# Motor_Shield.net
KiCad netlist of a schematic drawn in EAGLE
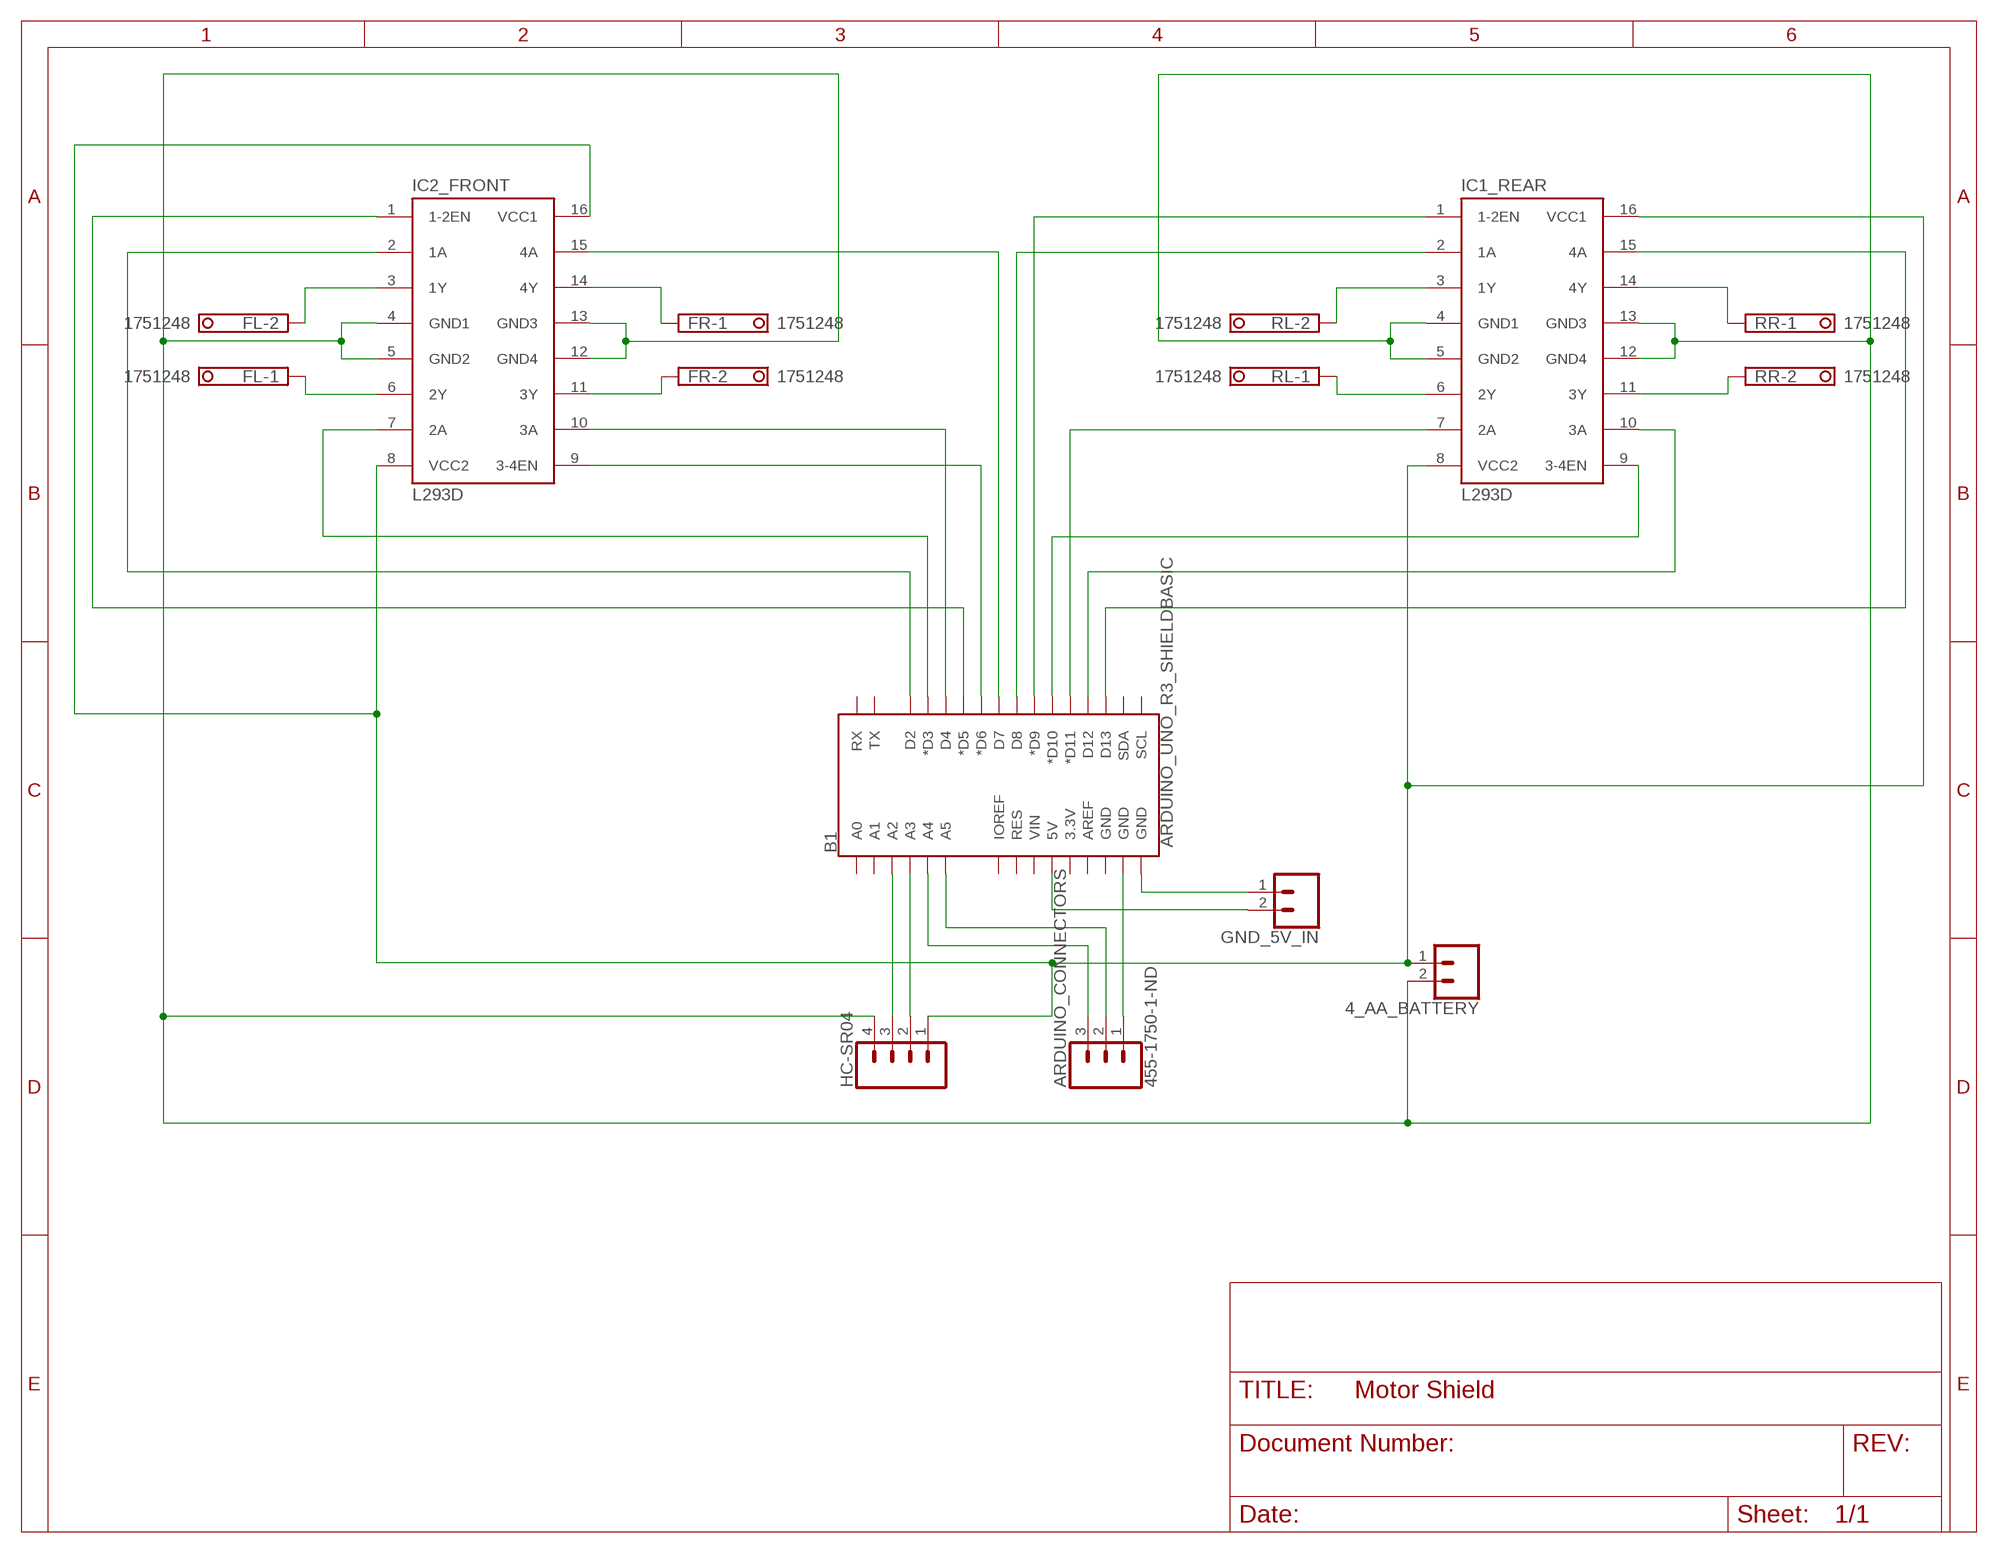
[diagram p0: schematic, sheet 1]

(export (version "E")
  (design (tool "Eeschema 10.0.6"))
  (components
    (comp (ref "4_AA_BATTERY")
      (value "CONN_02")
      (footprint "eagle-import:1X02")
      (libsource (lib "eagle-import") (part "CONN_02"))
    )
    (comp (ref "ARDUINO_CONNECTORS")
      (value "455-1750-1-ND")
      (footprint "eagle-import:1X03")
      (libsource (lib "eagle-import") (part "CONN_03"))
    )
    (comp (ref "B1")
      (value "ARDUINO_UNO_R3_SHIELDBASIC")
      (footprint "eagle-import:UNO_R3_SHIELD")
      (libsource (lib "eagle-import") (part "ARDUINO_UNO_R3_SHIELDBASIC"))
    )
    (comp (ref "FL")
      (value "1751248")
      (footprint "eagle-import:1751248")
      (libsource (lib "eagle-import") (part "1751248"))
    )
    (comp (ref "FR")
      (value "1751248")
      (footprint "eagle-import:1751248")
      (libsource (lib "eagle-import") (part "1751248"))
    )
    (comp (ref "GND_5V_IN")
      (value "CONN_02")
      (footprint "eagle-import:1X02")
      (libsource (lib "eagle-import") (part "CONN_02"))
    )
    (comp (ref "HC-SR04")
      (value "CONN_04PTH")
      (footprint "eagle-import:1X04")
      (libsource (lib "eagle-import") (part "CONN_04PTH"))
    )
    (comp (ref "IC1_REAR")
      (value "L293D")
      (footprint "eagle-import:DIL16")
      (libsource (lib "eagle-import") (part "L293D"))
    )
    (comp (ref "IC2_FRONT")
      (value "L293D")
      (footprint "eagle-import:DIL16")
      (libsource (lib "eagle-import") (part "L293D"))
    )
    (comp (ref "RL")
      (value "1751248")
      (footprint "eagle-import:1751248")
      (libsource (lib "eagle-import") (part "1751248"))
    )
    (comp (ref "RR")
      (value "1751248")
      (footprint "eagle-import:1751248")
      (libsource (lib "eagle-import") (part "1751248"))
    )
  )
  (nets
    (net (code "1") (name "Net-(ARDUINO_CONNECTORS-Pad1)") (class "Default")
      (node (ref "ARDUINO_CONNECTORS") (pin "1") (pinfunction "1_1") (pintype "passive"))
      (node (ref "B1") (pin "GND@1") (pinfunction "GND_GND@1") (pintype "bidirectional"))
    )
    (net (code "2") (name "Net-(ARDUINO_CONNECTORS-Pad2)") (class "Default")
      (node (ref "ARDUINO_CONNECTORS") (pin "2") (pinfunction "2_2") (pintype "passive"))
      (node (ref "B1") (pin "A5") (pinfunction "A5_A5") (pintype "bidirectional"))
    )
    (net (code "3") (name "Net-(ARDUINO_CONNECTORS-Pad3)") (class "Default")
      (node (ref "ARDUINO_CONNECTORS") (pin "3") (pinfunction "3_3") (pintype "passive"))
      (node (ref "B1") (pin "A4") (pinfunction "A4_A4") (pintype "bidirectional"))
    )
    (net (code "4") (name "Net-(B1-*D3)") (class "Default")
      (node (ref "B1") (pin "D3") (pinfunction "*D3_D3") (pintype "bidirectional"))
      (node (ref "IC2_FRONT") (pin "7") (pinfunction "2A_7") (pintype "input"))
    )
    (net (code "5") (name "Net-(B1-*D5)") (class "Default")
      (node (ref "B1") (pin "D5") (pinfunction "*D5_D5") (pintype "bidirectional"))
      (node (ref "IC2_FRONT") (pin "1") (pinfunction "1-2EN_1") (pintype "input"))
    )
    (net (code "6") (name "Net-(B1-*D6)") (class "Default")
      (node (ref "B1") (pin "D6") (pinfunction "*D6_D6") (pintype "bidirectional"))
      (node (ref "IC2_FRONT") (pin "9") (pinfunction "3-4EN_9") (pintype "input"))
    )
    (net (code "7") (name "Net-(B1-*D9)") (class "Default")
      (node (ref "B1") (pin "D9") (pinfunction "*D9_D9") (pintype "bidirectional"))
      (node (ref "IC1_REAR") (pin "1") (pinfunction "1-2EN_1") (pintype "input"))
    )
    (net (code "8") (name "Net-(B1-*D10)") (class "Default")
      (node (ref "B1") (pin "D10") (pinfunction "*D10_D10") (pintype "bidirectional"))
      (node (ref "IC1_REAR") (pin "9") (pinfunction "3-4EN_9") (pintype "input"))
    )
    (net (code "9") (name "Net-(B1-*D11)") (class "Default")
      (node (ref "B1") (pin "D11") (pinfunction "*D11_D11") (pintype "bidirectional"))
      (node (ref "IC1_REAR") (pin "7") (pinfunction "2A_7") (pintype "input"))
    )
    (net (code "10") (name "Net-(B1-GND-PadGND@0)") (class "Default")
      (node (ref "B1") (pin "GND@0") (pinfunction "GND_GND@0") (pintype "bidirectional"))
      (node (ref "GND_5V_IN") (pin "1") (pinfunction "1_1") (pintype "passive"))
    )
    (net (code "11") (name "Net-(B1-Pad5V)") (class "Default")
      (node (ref "B1") (pin "5V") (pinfunction "5V_5V") (pintype "bidirectional"))
      (node (ref "GND_5V_IN") (pin "2") (pinfunction "2_2") (pintype "passive"))
    )
    (net (code "12") (name "Net-(B1-PadA2)") (class "Default")
      (node (ref "B1") (pin "A2") (pinfunction "A2_A2") (pintype "bidirectional"))
      (node (ref "HC-SR04") (pin "3") (pinfunction "3_3") (pintype "passive"))
    )
    (net (code "13") (name "Net-(B1-PadA3)") (class "Default")
      (node (ref "B1") (pin "A3") (pinfunction "A3_A3") (pintype "bidirectional"))
      (node (ref "HC-SR04") (pin "2") (pinfunction "2_2") (pintype "passive"))
    )
    (net (code "14") (name "Net-(FLA-K)") (class "Default")
      (node (ref "FL") (pin "1") (pinfunction "K_1") (pintype "passive"))
      (node (ref "IC2_FRONT") (pin "6") (pinfunction "2Y_6") (pintype "output"))
    )
    (net (code "15") (name "Net-(FLB-K)") (class "Default")
      (node (ref "FL") (pin "2") (pinfunction "K_2") (pintype "passive"))
      (node (ref "IC2_FRONT") (pin "3") (pinfunction "1Y_3") (pintype "output"))
    )
    (net (code "16") (name "Net-(FRA-K)") (class "Default")
      (node (ref "FR") (pin "1") (pinfunction "K_1") (pintype "passive"))
      (node (ref "IC2_FRONT") (pin "14") (pinfunction "4Y_14") (pintype "output"))
    )
    (net (code "17") (name "Net-(FRB-K)") (class "Default")
      (node (ref "FR") (pin "2") (pinfunction "K_2") (pintype "passive"))
      (node (ref "IC2_FRONT") (pin "11") (pinfunction "3Y_11") (pintype "output"))
    )
    (net (code "18") (name "Net-(IC1_REAR-1A)") (class "Default")
      (node (ref "B1") (pin "D8") (pinfunction "D8_D8") (pintype "bidirectional"))
      (node (ref "IC1_REAR") (pin "2") (pinfunction "1A_2") (pintype "input"))
    )
    (net (code "19") (name "Net-(IC1_REAR-1Y)") (class "Default")
      (node (ref "IC1_REAR") (pin "3") (pinfunction "1Y_3") (pintype "output"))
      (node (ref "RL") (pin "2") (pinfunction "K_2") (pintype "passive"))
    )
    (net (code "20") (name "Net-(IC1_REAR-2Y)") (class "Default")
      (node (ref "IC1_REAR") (pin "6") (pinfunction "2Y_6") (pintype "output"))
      (node (ref "RL") (pin "1") (pinfunction "K_1") (pintype "passive"))
    )
    (net (code "21") (name "Net-(IC1_REAR-3A)") (class "Default")
      (node (ref "B1") (pin "D12") (pinfunction "D12_D12") (pintype "bidirectional"))
      (node (ref "IC1_REAR") (pin "10") (pinfunction "3A_10") (pintype "input"))
    )
    (net (code "22") (name "Net-(IC1_REAR-3Y)") (class "Default")
      (node (ref "IC1_REAR") (pin "11") (pinfunction "3Y_11") (pintype "output"))
      (node (ref "RR") (pin "2") (pinfunction "K_2") (pintype "passive"))
    )
    (net (code "23") (name "Net-(IC1_REAR-4A)") (class "Default")
      (node (ref "B1") (pin "D13") (pinfunction "D13_D13") (pintype "bidirectional"))
      (node (ref "IC1_REAR") (pin "15") (pinfunction "4A_15") (pintype "input"))
    )
    (net (code "24") (name "Net-(IC1_REAR-4Y)") (class "Default")
      (node (ref "IC1_REAR") (pin "14") (pinfunction "4Y_14") (pintype "output"))
      (node (ref "RR") (pin "1") (pinfunction "K_1") (pintype "passive"))
    )
    (net (code "25") (name "Net-(IC1_REAR-GND1)") (class "Default")
      (node (ref "4_AA_BATTERY") (pin "2") (pinfunction "2_2") (pintype "passive"))
      (node (ref "HC-SR04") (pin "4") (pinfunction "4_4") (pintype "passive"))
      (node (ref "IC1_REAR") (pin "12") (pinfunction "GND4_12") (pintype "power_in"))
      (node (ref "IC1_REAR") (pin "13") (pinfunction "GND3_13") (pintype "power_in"))
      (node (ref "IC1_REAR") (pin "4") (pinfunction "GND1_4") (pintype "power_in"))
      (node (ref "IC1_REAR") (pin "5") (pinfunction "GND2_5") (pintype "power_in"))
      (node (ref "IC2_FRONT") (pin "12") (pinfunction "GND4_12") (pintype "power_in"))
      (node (ref "IC2_FRONT") (pin "13") (pinfunction "GND3_13") (pintype "power_in"))
      (node (ref "IC2_FRONT") (pin "4") (pinfunction "GND1_4") (pintype "power_in"))
      (node (ref "IC2_FRONT") (pin "5") (pinfunction "GND2_5") (pintype "power_in"))
    )
    (net (code "26") (name "Net-(IC1_REAR-VCC1)") (class "Default")
      (node (ref "4_AA_BATTERY") (pin "1") (pinfunction "1_1") (pintype "passive"))
      (node (ref "HC-SR04") (pin "1") (pinfunction "1_1") (pintype "passive"))
      (node (ref "IC1_REAR") (pin "16") (pinfunction "VCC1_16") (pintype "power_in"))
      (node (ref "IC1_REAR") (pin "8") (pinfunction "VCC2_8") (pintype "power_in"))
      (node (ref "IC2_FRONT") (pin "16") (pinfunction "VCC1_16") (pintype "power_in"))
      (node (ref "IC2_FRONT") (pin "8") (pinfunction "VCC2_8") (pintype "power_in"))
    )
    (net (code "27") (name "Net-(IC2_FRONT-1A)") (class "Default")
      (node (ref "B1") (pin "D2") (pinfunction "D2_D2") (pintype "bidirectional"))
      (node (ref "IC2_FRONT") (pin "2") (pinfunction "1A_2") (pintype "input"))
    )
    (net (code "28") (name "Net-(IC2_FRONT-3A)") (class "Default")
      (node (ref "B1") (pin "D4") (pinfunction "D4_D4") (pintype "bidirectional"))
      (node (ref "IC2_FRONT") (pin "10") (pinfunction "3A_10") (pintype "input"))
    )
    (net (code "29") (name "Net-(IC2_FRONT-4A)") (class "Default")
      (node (ref "B1") (pin "D7") (pinfunction "D7_D7") (pintype "bidirectional"))
      (node (ref "IC2_FRONT") (pin "15") (pinfunction "4A_15") (pintype "input"))
    )
    (net (code "30") (name "unconnected-(B1-GND-PadGND@2)") (class "Default")
      (node (ref "B1") (pin "GND@2") (pinfunction "GND_GND@2") (pintype "bidirectional"))
    )
    (net (code "31") (name "unconnected-(B1-Pad3.3V)") (class "Default")
      (node (ref "B1") (pin "3.3V") (pinfunction "3.3V_3.3V") (pintype "bidirectional"))
    )
    (net (code "32") (name "unconnected-(B1-PadA0)") (class "Default")
      (node (ref "B1") (pin "A0") (pinfunction "A0_A0") (pintype "bidirectional"))
    )
    (net (code "33") (name "unconnected-(B1-PadA1)") (class "Default")
      (node (ref "B1") (pin "A1") (pinfunction "A1_A1") (pintype "bidirectional"))
    )
    (net (code "34") (name "unconnected-(B1-PadAREF)") (class "Default")
      (node (ref "B1") (pin "AREF") (pinfunction "AREF_AREF") (pintype "bidirectional"))
    )
    (net (code "35") (name "unconnected-(B1-PadIOREF)") (class "Default")
      (node (ref "B1") (pin "IOREF") (pinfunction "IOREF_IOREF") (pintype "bidirectional"))
    )
    (net (code "36") (name "unconnected-(B1-PadRES)") (class "Default")
      (node (ref "B1") (pin "RES") (pinfunction "RES_RES") (pintype "bidirectional"))
    )
    (net (code "37") (name "unconnected-(B1-PadRX)") (class "Default")
      (node (ref "B1") (pin "RX") (pinfunction "RX_RX") (pintype "bidirectional"))
    )
    (net (code "38") (name "unconnected-(B1-PadSCL)") (class "Default")
      (node (ref "B1") (pin "SCL") (pinfunction "SCL_SCL") (pintype "bidirectional"))
    )
    (net (code "39") (name "unconnected-(B1-PadSDA)") (class "Default")
      (node (ref "B1") (pin "SDA") (pinfunction "SDA_SDA") (pintype "bidirectional"))
    )
    (net (code "40") (name "unconnected-(B1-PadTX)") (class "Default")
      (node (ref "B1") (pin "TX") (pinfunction "TX_TX") (pintype "bidirectional"))
    )
    (net (code "41") (name "unconnected-(B1-PadVIN)") (class "Default")
      (node (ref "B1") (pin "VIN") (pinfunction "VIN_VIN") (pintype "bidirectional"))
    )
  )
)
